# PLD_I2C_Switch.net
KiCad netlist of a schematic drawn in Altium Designer
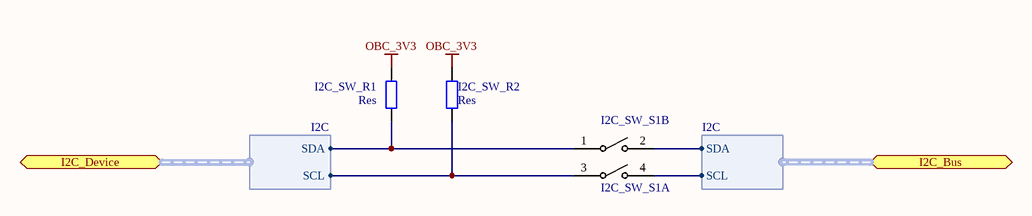
[diagram p0: PLD_I2C_Switch.SchDoc]

(export (version "E")
  (design (tool "Eeschema 10.0.6"))
  (components
    (comp (ref "I2C_SW_R1")
      (value "Res")
      (footprint "SMD_Resistor_0603")
      (libsource (lib "resistors") (part "Res"))
    )
    (comp (ref "I2C_SW_R2")
      (value "Res")
      (footprint "SMD_Resistor_0603")
      (libsource (lib "resistors") (part "Res"))
    )
    (comp (ref "I2C_SW_S1")
      (value "MCEPM-02")
      (footprint "MCEPM-02")
      (libsource (lib "switches") (part "MCEPM-02"))
    )
  )
  (nets
    (net (code "3") (name "Net-(I2C_SW_R1-Pad2)") (class "Default")
      (node (ref "I2C_SW_R1") (pin "2") (pinfunction "2_2") (pintype "passive"))
      (node (ref "I2C_SW_S1") (pin "1") (pinfunction "1_1") (pintype "passive"))
    )
    (net (code "4") (name "Net-(I2C_SW_R2-Pad2)") (class "Default")
      (node (ref "I2C_SW_R2") (pin "2") (pinfunction "2_2") (pintype "passive"))
      (node (ref "I2C_SW_S1") (pin "3") (pinfunction "3_3") (pintype "passive"))
    )
    (net (code "5") (name "OBC_3V3") (class "Default")
      (node (ref "I2C_SW_R1") (pin "1") (pinfunction "1_1") (pintype "passive"))
      (node (ref "I2C_SW_R2") (pin "1") (pinfunction "1_1") (pintype "passive"))
    )
    (net (code "6") (name "unconnected-(I2C_SW_S1-Pad2)") (class "Default")
      (node (ref "I2C_SW_S1") (pin "2") (pinfunction "2_2") (pintype "passive"))
    )
    (net (code "7") (name "unconnected-(I2C_SW_S1-Pad4)") (class "Default")
      (node (ref "I2C_SW_S1") (pin "4") (pinfunction "4_4") (pintype "passive"))
    )
  )
)
